# 9_Airframe-Wireless_-_Kopie.net
KiCad netlist of a schematic drawn in Altium Designer
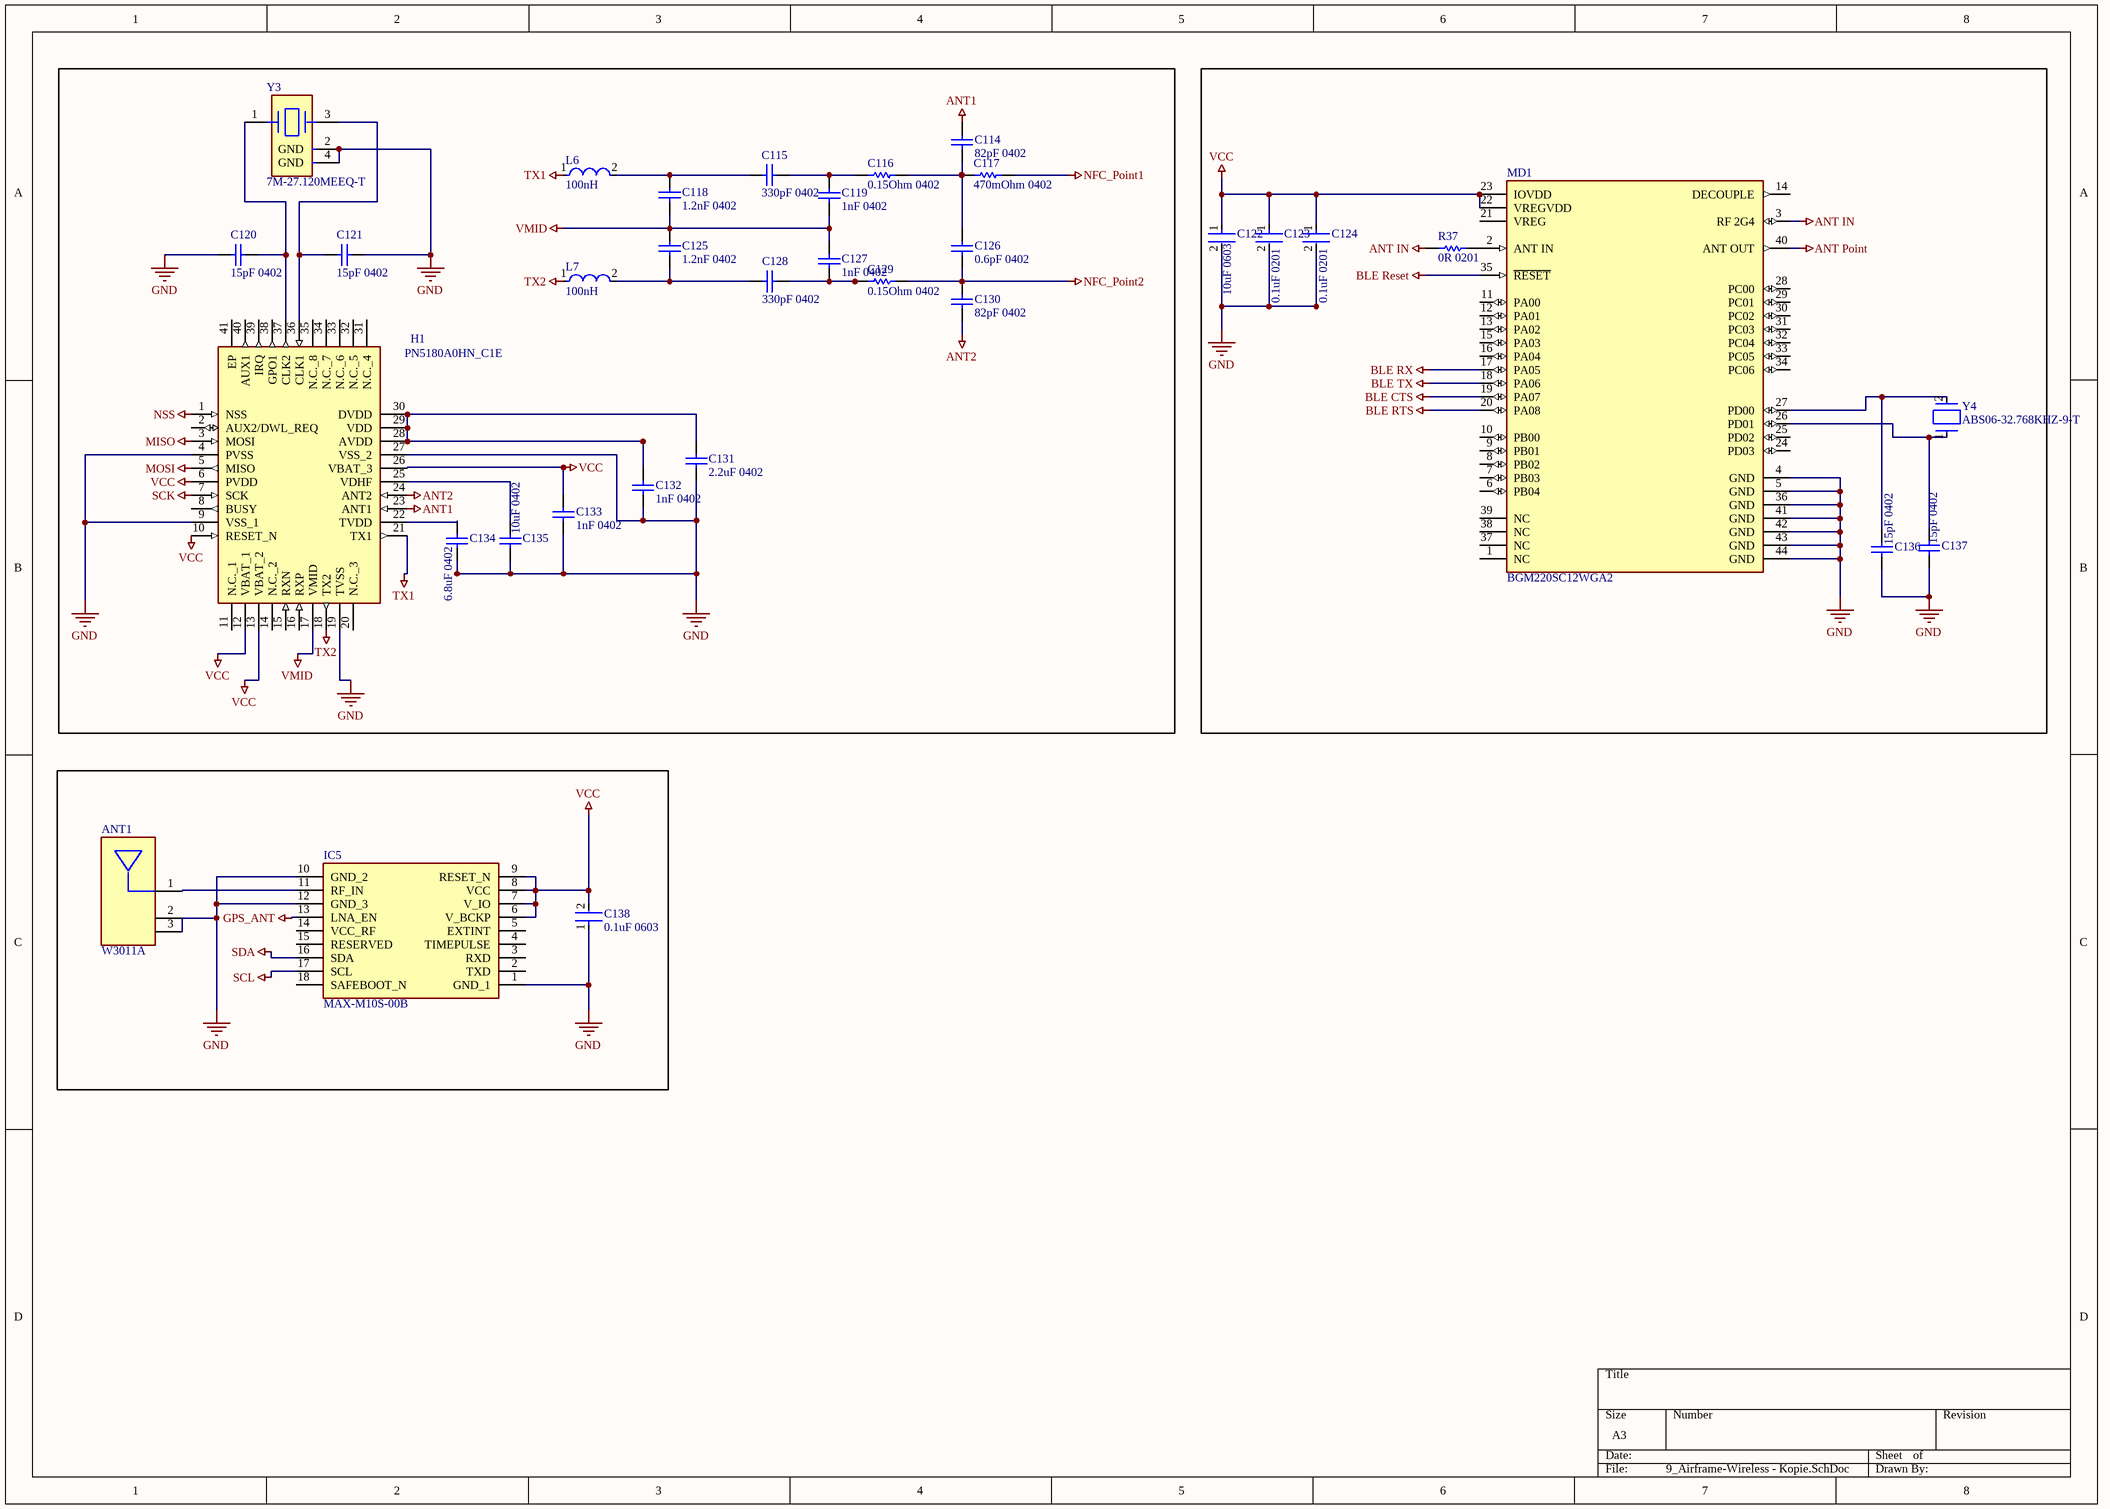
[diagram p0: 9_Airframe-Wireless - Kopie.SchDoc]

(export (version "E")
  (design (tool "Eeschema 10.0.6"))
  (components
    (comp (ref "ANT1")
      (value "W3011A")
      (footprint "FP-W3011A-MFG")
      (description "RF ANT 1.575GHZ CHIP SOLDER SMD")
      (fields
        (field (name "OCTOPART") "https://octopart.com/w3011a-pulse-10684180")
        (field (name "MANUFACTURER") "PulseLarsen Antennas")
      )
      (libsource (lib "Altium Content Vault") (part "6d32a7a60510b62759eb526d3a7a656"))
    )
    (comp (ref "C114")
      (value "82pF 0402")
      (footprint "CAPC1005X55X25ML5T10")
      (description "Chip Capacitor, 1 nF, +/- 10%, 50 V, -55 to 125 degC, 0402 (1005 Metric), RoHS, Tape and Reel")
      (fields (field (name "TOLERANCE") "10%"))
      (libsource (lib "Altium Content Vault") (part "CAP-NP-2"))
    )
    (comp (ref "C115")
      (value "330pF 0402")
      (footprint "CAPC1005X55X25ML5T10")
      (description "Chip Capacitor, 1 nF, +/- 10%, 50 V, -55 to 125 degC, 0402 (1005 Metric), RoHS, Tape and Reel")
      (fields (field (name "TOLERANCE") "10%"))
      (libsource (lib "Altium Content Vault") (part "CAP-NP-2"))
    )
    (comp (ref "C116")
      (value "0.15Ohm 0402")
      (footprint "RESC1608X55X25ML10T15")
      (description "Chip Resistor, 0 Ohm, +/- 5%, 0.1 W, -55 to 155 degC, 0603 (1608 Metric), RoHS, Tape and Reel")
      (fields (field (name "TOLERANCE") "5%") (field (name "MANUFACTURER") "Yageo"))
      (libsource (lib "Altium Content Vault") (part "RES-2"))
    )
    (comp (ref "C117")
      (value "470mOhm 0402")
      (footprint "RESC1608X55X25ML10T15")
      (description "Chip Resistor, 0 Ohm, +/- 5%, 0.1 W, -55 to 155 degC, 0603 (1608 Metric), RoHS, Tape and Reel")
      (fields (field (name "TOLERANCE") "5%") (field (name "MANUFACTURER") "Yageo"))
      (libsource (lib "Altium Content Vault") (part "RES-2"))
    )
    (comp (ref "C118")
      (value "1.2nF 0402")
      (footprint "CAPC1005X55X25ML5T10")
      (description "Chip Capacitor, 1 nF, +/- 10%, 50 V, -55 to 125 degC, 0402 (1005 Metric), RoHS, Tape and Reel")
      (fields (field (name "TOLERANCE") "10%"))
      (libsource (lib "Altium Content Vault") (part "CAP-NP-2"))
    )
    (comp (ref "C119")
      (value "1nF 0402")
      (footprint "CAPC1005X55X25ML5T10")
      (description "Chip Capacitor, 1 nF, +/- 10%, 50 V, -55 to 125 degC, 0402 (1005 Metric), RoHS, Tape and Reel")
      (fields (field (name "TOLERANCE") "10%"))
      (libsource (lib "Altium Content Vault") (part "CAP-NP-2"))
    )
    (comp (ref "C120")
      (value "15pF 0402")
      (footprint "CAPC1005X55X25ML5T10")
      (description "Chip Capacitor, 1 nF, +/- 10%, 50 V, -55 to 125 degC, 0402 (1005 Metric), RoHS, Tape and Reel")
      (fields (field (name "TOLERANCE") "10%"))
      (libsource (lib "Altium Content Vault") (part "CAP-NP-2"))
    )
    (comp (ref "C121")
      (value "15pF 0402")
      (footprint "CAPC1005X55X25ML5T10")
      (description "Chip Capacitor, 1 nF, +/- 10%, 50 V, -55 to 125 degC, 0402 (1005 Metric), RoHS, Tape and Reel")
      (fields (field (name "TOLERANCE") "10%"))
      (libsource (lib "Altium Content Vault") (part "CAP-NP-2"))
    )
    (comp (ref "C122")
      (value "10uF 0603")
      (footprint "FP-GRM188-0_2-IPC_C")
      (description "Chip Multilayer Ceramic Capacitors for General Purpose, 0603, 22uF, X5R, 15%, 20%, 10V")
      (fields (field (name "TOLERANCE") "20%"))
      (libsource (lib "Altium Content Vault") (part "11868f565c42a9108669ba33697ecf6"))
    )
    (comp (ref "C123")
      (value "0.1uF 0201")
      (footprint "FP-C0603-030-0_03-IPC_C")
      (description "Multilayer Ceramic Capacitors 220nF ±10% 6.3V X6S SMD 0201")
      (fields (field (name "TOLERANCE") "10%"))
      (libsource (lib "Altium Content Vault") (part "02cd4be3c70576c341d710602a673aa"))
    )
    (comp (ref "C124")
      (value "0.1uF 0201")
      (footprint "FP-C0603-030-0_03-IPC_C")
      (description "Multilayer Ceramic Capacitors 220nF ±10% 6.3V X6S SMD 0201")
      (fields (field (name "TOLERANCE") "10%"))
      (libsource (lib "Altium Content Vault") (part "02cd4be3c70576c341d710602a673aa"))
    )
    (comp (ref "C125")
      (value "1.2nF 0402")
      (footprint "CAPC1005X55X25ML5T10")
      (description "Chip Capacitor, 1 nF, +/- 10%, 50 V, -55 to 125 degC, 0402 (1005 Metric), RoHS, Tape and Reel")
      (fields (field (name "TOLERANCE") "10%"))
      (libsource (lib "Altium Content Vault") (part "CAP-NP-2"))
    )
    (comp (ref "C126")
      (value "0.6pF 0402")
      (footprint "CAPC1005X55X25ML5T10")
      (description "Chip Capacitor, 1 nF, +/- 10%, 50 V, -55 to 125 degC, 0402 (1005 Metric), RoHS, Tape and Reel")
      (fields (field (name "TOLERANCE") "10%"))
      (libsource (lib "Altium Content Vault") (part "CAP-NP-2"))
    )
    (comp (ref "C127")
      (value "1nF 0402")
      (footprint "CAPC1005X55X25ML5T10")
      (description "Chip Capacitor, 1 nF, +/- 10%, 50 V, -55 to 125 degC, 0402 (1005 Metric), RoHS, Tape and Reel")
      (fields (field (name "TOLERANCE") "10%"))
      (libsource (lib "Altium Content Vault") (part "CAP-NP-2"))
    )
    (comp (ref "C128")
      (value "330pF 0402")
      (footprint "CAPC1005X55X25ML5T10")
      (description "Chip Capacitor, 1 nF, +/- 10%, 50 V, -55 to 125 degC, 0402 (1005 Metric), RoHS, Tape and Reel")
      (fields (field (name "TOLERANCE") "10%"))
      (libsource (lib "Altium Content Vault") (part "CAP-NP-2"))
    )
    (comp (ref "C129")
      (value "0.15Ohm 0402")
      (footprint "RESC1608X55X25ML10T15")
      (description "Chip Resistor, 0 Ohm, +/- 5%, 0.1 W, -55 to 155 degC, 0603 (1608 Metric), RoHS, Tape and Reel")
      (fields (field (name "TOLERANCE") "5%") (field (name "MANUFACTURER") "Yageo"))
      (libsource (lib "Altium Content Vault") (part "RES-2"))
    )
    (comp (ref "C130")
      (value "82pF 0402")
      (footprint "CAPC1005X55X25ML5T10")
      (description "Chip Capacitor, 1 nF, +/- 10%, 50 V, -55 to 125 degC, 0402 (1005 Metric), RoHS, Tape and Reel")
      (fields (field (name "TOLERANCE") "10%"))
      (libsource (lib "Altium Content Vault") (part "CAP-NP-2"))
    )
    (comp (ref "C131")
      (value "2.2uF 0402")
      (footprint "CAPC1005X55X25ML5T10")
      (description "Chip Capacitor, 1 nF, +/- 10%, 50 V, -55 to 125 degC, 0402 (1005 Metric), RoHS, Tape and Reel")
      (fields (field (name "TOLERANCE") "10%"))
      (libsource (lib "Altium Content Vault") (part "CAP-NP-2"))
    )
    (comp (ref "C132")
      (value "1nF 0402")
      (footprint "CAPC1005X55X25ML5T10")
      (description "Chip Capacitor, 1 nF, +/- 10%, 50 V, -55 to 125 degC, 0402 (1005 Metric), RoHS, Tape and Reel")
      (fields (field (name "TOLERANCE") "10%"))
      (libsource (lib "Altium Content Vault") (part "CAP-NP-2"))
    )
    (comp (ref "C133")
      (value "1nF 0402")
      (footprint "CAPC1005X55X25ML5T10")
      (description "Chip Capacitor, 1 nF, +/- 10%, 50 V, -55 to 125 degC, 0402 (1005 Metric), RoHS, Tape and Reel")
      (fields (field (name "TOLERANCE") "10%"))
      (libsource (lib "Altium Content Vault") (part "CAP-NP-2"))
    )
    (comp (ref "C134")
      (value "6.8uF 0402")
      (footprint "CAPC1005X55X25ML5T10")
      (description "Chip Capacitor, 1 nF, +/- 10%, 50 V, -55 to 125 degC, 0402 (1005 Metric), RoHS, Tape and Reel")
      (fields (field (name "TOLERANCE") "10%"))
      (libsource (lib "Altium Content Vault") (part "CAP-NP-2"))
    )
    (comp (ref "C135")
      (value "10uF 0402")
      (footprint "CAPC1005X55X25ML5T10")
      (description "Chip Capacitor, 1 nF, +/- 10%, 50 V, -55 to 125 degC, 0402 (1005 Metric), RoHS, Tape and Reel")
      (fields (field (name "TOLERANCE") "10%"))
      (libsource (lib "Altium Content Vault") (part "CAP-NP-2"))
    )
    (comp (ref "C136")
      (value "15pF 0402")
      (footprint "CAPC1005X55X25ML5T10")
      (description "Chip Capacitor, 1 nF, +/- 10%, 50 V, -55 to 125 degC, 0402 (1005 Metric), RoHS, Tape and Reel")
      (fields (field (name "TOLERANCE") "10%"))
      (libsource (lib "Altium Content Vault") (part "CAP-NP-2"))
    )
    (comp (ref "C137")
      (value "15pF 0402")
      (footprint "CAPC1005X55X25ML5T10")
      (description "Chip Capacitor, 1 nF, +/- 10%, 50 V, -55 to 125 degC, 0402 (1005 Metric), RoHS, Tape and Reel")
      (fields (field (name "TOLERANCE") "10%"))
      (libsource (lib "Altium Content Vault") (part "CAP-NP-2"))
    )
    (comp (ref "C138")
      (value "0.1uF 0603")
      (footprint "FP-C0603C-CF-MFG")
      (description "CAP CER 0.1UF 50V X7R 0603")
      (fields (field (name "TOLERANCE") "0.1") (field (name "MANUFACTURER") "KEMET"))
      (libsource (lib "Altium Content Vault") (part "b4654b650e69147ec39a6b967a45e02"))
    )
    (comp (ref "H1")
      (value "PN5180A0HN_C1E")
      (footprint "SamacSys:QFN50P600X600X100-41N-D")
      (description "Hardware")
      (fields
        (field (name "MANUFACTURER_PART_NUMBER") "PN5180A0HN/C1E")
        (field (name "MOUSER PART NUMBER") "771-PN5180A0HN/C1E")
      )
      (libsource (lib "*") (part "PN5180A0HN_C1E"))
    )
    (comp (ref "IC5")
      (value "MAX-M10S-00B")
      (footprint "SamacSys:MAXM10S00B")
      (description "Integrated Circuit")
      (fields (field (name "MOUSER PART NUMBER") "377-MAX-M10S-00B"))
      (libsource (lib "*") (part "MAX-M10S-00B"))
    )
    (comp (ref "L6")
      (value "100nH")
      (footprint "FP-LQM18NN_00-IPC_C")
      (description "Multilayer Type Inductor for General Circuits, 0603 (1608), 100nH, 10%, 0.5Ω, 50mA")
      (fields (field (name "TOLERANCE") "10%"))
      (libsource (lib "Altium Content Vault") (part "725321dda6339637d4d059423bc1c3c"))
    )
    (comp (ref "L7")
      (value "100nH")
      (footprint "FP-LQM18NN_00-IPC_C")
      (description "Multilayer Type Inductor for General Circuits, 0603 (1608), 100nH, 10%, 0.5Ω, 50mA")
      (fields (field (name "TOLERANCE") "10%"))
      (libsource (lib "Altium Content Vault") (part "725321dda6339637d4d059423bc1c3c"))
    )
    (comp (ref "MD1")
      (value "BGM220SC12WGA2")
      (footprint "FP-BGM220SC12WGA2-MFG")
      (description "WIRELESS GECKO, BLUETOOTH SIP MO")
      (libsource (lib "Altium Content Vault") (part "a291eb52f76d4e7f0fdfcca3ce5d403"))
    )
    (comp (ref "R37")
      (value "0R 0201")
      (footprint "RESC0603X28X15NL05T05")
      (fields (field (name "MANUFACTURER") "Vishay") (field (name "PART NUMBER") "CRCW0201100RFNED"))
      (libsource (lib "Altium Content Vault") (part "RES"))
    )
    (comp (ref "Y3")
      (value "7M-27.120MEEQ-T")
      (footprint "FP-7M-MFG")
      (description "Crystal 27.12MHz, 10ppm, 10pF, 50Ω")
      (fields (field (name "TOLERANCE") "10ppm"))
      (libsource (lib "Altium Content Vault") (part "41079aabb0e87794b56622915be14ed"))
    )
    (comp (ref "Y4")
      (value "ABS06-32.768KHZ-9-T")
      (footprint "FP-ABS06-MFG")
      (description "Crystal 32.768kHz ±20ppm (Tol) 9pF FUND 90kΩ 2-Pin Mini-CSMD T/R")
      (fields (field (name "TOLERANCE") "20ppm"))
      (libsource (lib "Altium Content Vault") (part "c23a69dc6c9e2f18f2079038eb95dd1"))
    )
  )
  (nets
    (net (code "1") (name "ANT IN") (class "Default")
      (node (ref "MD1") (pin "3") (pinfunction "RF_2G4_3") (pintype "bidirectional"))
      (node (ref "R37") (pin "2") (pinfunction "2_2") (pintype "passive"))
    )
    (net (code "2") (name "ANT Point") (class "Default")
      (node (ref "MD1") (pin "40") (pinfunction "ANT_OUT_40") (pintype "output"))
    )
    (net (code "3") (name "ANT1") (class "Default")
      (node (ref "C114") (pin "1") (pinfunction "1_1") (pintype "passive"))
      (node (ref "H1") (pin "23") (pinfunction "ANT1_23") (pintype "input"))
    )
    (net (code "4") (name "ANT2") (class "Default")
      (node (ref "C130") (pin "2") (pinfunction "2_2") (pintype "passive"))
      (node (ref "H1") (pin "24") (pinfunction "ANT2_24") (pintype "input"))
    )
    (net (code "5") (name "BLE CTS") (class "Default")
      (node (ref "MD1") (pin "19") (pinfunction "PA07_19") (pintype "bidirectional"))
    )
    (net (code "6") (name "BLE RTS") (class "Default")
      (node (ref "MD1") (pin "20") (pinfunction "PA08_20") (pintype "bidirectional"))
    )
    (net (code "7") (name "BLE RX") (class "Default")
      (node (ref "MD1") (pin "17") (pinfunction "PA05_17") (pintype "bidirectional"))
    )
    (net (code "8") (name "BLE Reset") (class "Default")
      (node (ref "MD1") (pin "35") (pinfunction "~{RESET}_35") (pintype "input"))
    )
    (net (code "9") (name "BLE TX") (class "Default")
      (node (ref "MD1") (pin "18") (pinfunction "PA06_18") (pintype "bidirectional"))
    )
    (net (code "10") (name "GND") (class "Default")
      (node (ref "ANT1") (pin "2") (pinfunction "GND_2") (pintype "power_in"))
      (node (ref "ANT1") (pin "3") (pinfunction "GND_3") (pintype "power_in"))
      (node (ref "C120") (pin "1") (pinfunction "1_1") (pintype "passive"))
      (node (ref "C121") (pin "2") (pinfunction "2_2") (pintype "passive"))
      (node (ref "C122") (pin "2") (pinfunction "2_2") (pintype "passive"))
      (node (ref "C123") (pin "2") (pinfunction "2_2") (pintype "passive"))
      (node (ref "C124") (pin "2") (pinfunction "2_2") (pintype "passive"))
      (node (ref "C131") (pin "2") (pinfunction "2_2") (pintype "passive"))
      (node (ref "C132") (pin "2") (pinfunction "2_2") (pintype "passive"))
      (node (ref "C133") (pin "2") (pinfunction "2_2") (pintype "passive"))
      (node (ref "C134") (pin "2") (pinfunction "2_2") (pintype "passive"))
      (node (ref "C135") (pin "2") (pinfunction "2_2") (pintype "passive"))
      (node (ref "C136") (pin "1") (pinfunction "1_1") (pintype "passive"))
      (node (ref "C137") (pin "1") (pinfunction "1_1") (pintype "passive"))
      (node (ref "C138") (pin "1") (pinfunction "1_1") (pintype "passive"))
      (node (ref "H1") (pin "19") (pinfunction "TVSS_19") (pintype "power_in"))
      (node (ref "H1") (pin "27") (pinfunction "VSS_2_27") (pintype "power_in"))
      (node (ref "H1") (pin "4") (pinfunction "PVSS_4") (pintype "power_in"))
      (node (ref "H1") (pin "9") (pinfunction "VSS_1_9") (pintype "power_in"))
      (node (ref "IC5") (pin "1") (pinfunction "GND_1_1") (pintype "passive"))
      (node (ref "IC5") (pin "10") (pinfunction "GND_2_10") (pintype "passive"))
      (node (ref "IC5") (pin "12") (pinfunction "GND_3_12") (pintype "passive"))
      (node (ref "MD1") (pin "36") (pinfunction "GND_36") (pintype "power_in"))
      (node (ref "MD1") (pin "4") (pinfunction "GND_4") (pintype "power_in"))
      (node (ref "MD1") (pin "41") (pinfunction "GND_41") (pintype "power_in"))
      (node (ref "MD1") (pin "42") (pinfunction "GND_42") (pintype "power_in"))
      (node (ref "MD1") (pin "43") (pinfunction "GND_43") (pintype "power_in"))
      (node (ref "MD1") (pin "44") (pinfunction "GND_44") (pintype "power_in"))
      (node (ref "MD1") (pin "5") (pinfunction "GND_5") (pintype "power_in"))
      (node (ref "Y3") (pin "2") (pinfunction "GND_2") (pintype "power_in"))
      (node (ref "Y3") (pin "4") (pinfunction "GND_4") (pintype "power_in"))
    )
    (net (code "11") (name "GPS_ANT") (class "Default")
      (node (ref "IC5") (pin "13") (pinfunction "LNA_EN_13") (pintype "passive"))
    )
    (net (code "12") (name "MISO") (class "Default")
      (node (ref "H1") (pin "3") (pinfunction "MOSI_3") (pintype "input"))
    )
    (net (code "13") (name "MOSI") (class "Default")
      (node (ref "H1") (pin "5") (pinfunction "MISO_5") (pintype "output"))
    )
    (net (code "14") (name "NFC_Point1") (class "Default")
      (node (ref "C117") (pin "1") (pinfunction "1_1") (pintype "passive"))
    )
    (net (code "15") (name "NFC_Point2") (class "Default")
      (node (ref "C126") (pin "2") (pinfunction "2_2") (pintype "passive"))
      (node (ref "C129") (pin "1") (pinfunction "1_1") (pintype "passive"))
      (node (ref "C130") (pin "1") (pinfunction "1_1") (pintype "passive"))
    )
    (net (code "16") (name "NSS") (class "Default")
      (node (ref "H1") (pin "1") (pinfunction "NSS_1") (pintype "input"))
    )
    (net (code "17") (name "Net-(ANT1-Feed)") (class "Default")
      (node (ref "ANT1") (pin "1") (pinfunction "Feed_1") (pintype "power_in"))
      (node (ref "IC5") (pin "11") (pinfunction "RF_IN_11") (pintype "passive"))
    )
    (net (code "18") (name "Net-(C114-Pad2)") (class "Default")
      (node (ref "C114") (pin "2") (pinfunction "2_2") (pintype "passive"))
      (node (ref "C116") (pin "1") (pinfunction "1_1") (pintype "passive"))
      (node (ref "C117") (pin "2") (pinfunction "2_2") (pintype "passive"))
      (node (ref "C126") (pin "1") (pinfunction "1_1") (pintype "passive"))
    )
    (net (code "19") (name "Net-(C115-Pad1)") (class "Default")
      (node (ref "C115") (pin "1") (pinfunction "1_1") (pintype "passive"))
      (node (ref "C118") (pin "1") (pinfunction "1_1") (pintype "passive"))
      (node (ref "L6") (pin "2") (pinfunction "2_2") (pintype "passive"))
    )
    (net (code "20") (name "Net-(C115-Pad2)") (class "Default")
      (node (ref "C115") (pin "2") (pinfunction "2_2") (pintype "passive"))
      (node (ref "C116") (pin "2") (pinfunction "2_2") (pintype "passive"))
      (node (ref "C119") (pin "2") (pinfunction "2_2") (pintype "passive"))
    )
    (net (code "21") (name "Net-(C125-Pad2)") (class "Default")
      (node (ref "C125") (pin "2") (pinfunction "2_2") (pintype "passive"))
      (node (ref "C128") (pin "1") (pinfunction "1_1") (pintype "passive"))
      (node (ref "L7") (pin "2") (pinfunction "2_2") (pintype "passive"))
    )
    (net (code "22") (name "Net-(C127-Pad1)") (class "Default")
      (node (ref "C127") (pin "1") (pinfunction "1_1") (pintype "passive"))
      (node (ref "C128") (pin "2") (pinfunction "2_2") (pintype "passive"))
      (node (ref "C129") (pin "2") (pinfunction "2_2") (pintype "passive"))
    )
    (net (code "23") (name "Net-(H1-AVDD)") (class "Default")
      (node (ref "C131") (pin "1") (pinfunction "1_1") (pintype "passive"))
      (node (ref "C132") (pin "1") (pinfunction "1_1") (pintype "passive"))
      (node (ref "H1") (pin "28") (pinfunction "AVDD_28") (pintype "power_in"))
      (node (ref "H1") (pin "29") (pinfunction "VDD_29") (pintype "power_in"))
      (node (ref "H1") (pin "30") (pinfunction "DVDD_30") (pintype "power_in"))
    )
    (net (code "24") (name "Net-(H1-CLK1)") (class "Default")
      (node (ref "C121") (pin "1") (pinfunction "1_1") (pintype "passive"))
      (node (ref "H1") (pin "36") (pinfunction "CLK1_36") (pintype "input"))
      (node (ref "Y3") (pin "3") (pinfunction "3_3") (pintype "passive"))
    )
    (net (code "25") (name "Net-(H1-CLK2)") (class "Default")
      (node (ref "C120") (pin "2") (pinfunction "2_2") (pintype "passive"))
      (node (ref "H1") (pin "37") (pinfunction "CLK2_37") (pintype "output"))
      (node (ref "Y3") (pin "1") (pinfunction "1_1") (pintype "passive"))
    )
    (net (code "26") (name "Net-(H1-TVDD)") (class "Default")
      (node (ref "C134") (pin "1") (pinfunction "1_1") (pintype "passive"))
      (node (ref "H1") (pin "22") (pinfunction "TVDD_22") (pintype "power_in"))
    )
    (net (code "27") (name "Net-(H1-VDHF)") (class "Default")
      (node (ref "C135") (pin "1") (pinfunction "1_1") (pintype "passive"))
      (node (ref "H1") (pin "25") (pinfunction "VDHF_25") (pintype "power_in"))
    )
    (net (code "28") (name "Net-(MD1-ANT_IN)") (class "Default")
      (node (ref "MD1") (pin "2") (pinfunction "ANT_IN_2") (pintype "input"))
      (node (ref "R37") (pin "1") (pinfunction "1_1") (pintype "passive"))
    )
    (net (code "29") (name "Net-(MD1-PD00)") (class "Default")
      (node (ref "C136") (pin "2") (pinfunction "2_2") (pintype "passive"))
      (node (ref "MD1") (pin "27") (pinfunction "PD00_27") (pintype "bidirectional"))
      (node (ref "Y4") (pin "2") (pinfunction "2_2") (pintype "passive"))
    )
    (net (code "30") (name "Net-(MD1-PD01)") (class "Default")
      (node (ref "C137") (pin "2") (pinfunction "2_2") (pintype "passive"))
      (node (ref "MD1") (pin "26") (pinfunction "PD01_26") (pintype "bidirectional"))
      (node (ref "Y4") (pin "1") (pinfunction "1_1") (pintype "passive"))
    )
    (net (code "31") (name "SCK") (class "Default")
      (node (ref "H1") (pin "7") (pinfunction "SCK_7") (pintype "input"))
    )
    (net (code "32") (name "SCL") (class "Default")
      (node (ref "IC5") (pin "17") (pinfunction "SCL_17") (pintype "passive"))
    )
    (net (code "33") (name "SDA") (class "Default")
      (node (ref "IC5") (pin "16") (pinfunction "SDA_16") (pintype "passive"))
    )
    (net (code "34") (name "TX1") (class "Default")
      (node (ref "H1") (pin "21") (pinfunction "TX1_21") (pintype "output"))
      (node (ref "L6") (pin "1") (pinfunction "1_1") (pintype "passive"))
    )
    (net (code "35") (name "TX2") (class "Default")
      (node (ref "H1") (pin "18") (pinfunction "TX2_18") (pintype "output"))
      (node (ref "L7") (pin "1") (pinfunction "1_1") (pintype "passive"))
    )
    (net (code "36") (name "VCC") (class "Default")
      (node (ref "C122") (pin "1") (pinfunction "1_1") (pintype "passive"))
      (node (ref "C123") (pin "1") (pinfunction "1_1") (pintype "passive"))
      (node (ref "C124") (pin "1") (pinfunction "1_1") (pintype "passive"))
      (node (ref "C133") (pin "1") (pinfunction "1_1") (pintype "passive"))
      (node (ref "C138") (pin "2") (pinfunction "2_2") (pintype "passive"))
      (node (ref "H1") (pin "10") (pinfunction "RESET_N_10") (pintype "input"))
      (node (ref "H1") (pin "12") (pinfunction "VBAT_1_12") (pintype "power_in"))
      (node (ref "H1") (pin "13") (pinfunction "VBAT_2_13") (pintype "power_in"))
      (node (ref "H1") (pin "26") (pinfunction "VBAT_3_26") (pintype "power_in"))
      (node (ref "H1") (pin "6") (pinfunction "PVDD_6") (pintype "power_in"))
      (node (ref "IC5") (pin "6") (pinfunction "V_BCKP_6") (pintype "passive"))
      (node (ref "IC5") (pin "7") (pinfunction "V_IO_7") (pintype "passive"))
      (node (ref "IC5") (pin "8") (pinfunction "VCC_8") (pintype "passive"))
      (node (ref "IC5") (pin "9") (pinfunction "RESET_N_9") (pintype "passive"))
      (node (ref "MD1") (pin "22") (pinfunction "VREGVDD_22") (pintype "power_in"))
      (node (ref "MD1") (pin "23") (pinfunction "IOVDD_23") (pintype "power_in"))
    )
    (net (code "37") (name "VMID") (class "Default")
      (node (ref "C118") (pin "2") (pinfunction "2_2") (pintype "passive"))
      (node (ref "C119") (pin "1") (pinfunction "1_1") (pintype "passive"))
      (node (ref "C125") (pin "1") (pinfunction "1_1") (pintype "passive"))
      (node (ref "C127") (pin "2") (pinfunction "2_2") (pintype "passive"))
      (node (ref "H1") (pin "17") (pinfunction "VMID_17") (pintype "power_in"))
    )
    (net (code "38") (name "unconnected-(H1-AUX1-Pad40)") (class "Default")
      (node (ref "H1") (pin "40") (pinfunction "AUX1_40") (pintype "output"))
    )
    (net (code "39") (name "unconnected-(H1-AUX2{slash}DWL_REQ-Pad2)") (class "Default")
      (node (ref "H1") (pin "2") (pinfunction "AUX2/DWL_REQ_2") (pintype "bidirectional"))
    )
    (net (code "40") (name "unconnected-(H1-BUSY-Pad8)") (class "Default")
      (node (ref "H1") (pin "8") (pinfunction "BUSY_8") (pintype "output"))
    )
    (net (code "41") (name "unconnected-(H1-EP-Pad41)") (class "Default")
      (node (ref "H1") (pin "41") (pinfunction "EP_41") (pintype "passive"))
    )
    (net (code "42") (name "unconnected-(H1-GPO1-Pad38)") (class "Default")
      (node (ref "H1") (pin "38") (pinfunction "GPO1_38") (pintype "output"))
    )
    (net (code "43") (name "unconnected-(H1-IRQ-Pad39)") (class "Default")
      (node (ref "H1") (pin "39") (pinfunction "IRQ_39") (pintype "output"))
    )
    (net (code "44") (name "unconnected-(H1-N.C._1-Pad11)") (class "Default")
      (node (ref "H1") (pin "11") (pinfunction "N.C._1_11") (pintype "passive"))
    )
    (net (code "45") (name "unconnected-(H1-N.C._2-Pad14)") (class "Default")
      (node (ref "H1") (pin "14") (pinfunction "N.C._2_14") (pintype "passive"))
    )
    (net (code "46") (name "unconnected-(H1-N.C._3-Pad20)") (class "Default")
      (node (ref "H1") (pin "20") (pinfunction "N.C._3_20") (pintype "passive"))
    )
    (net (code "47") (name "unconnected-(H1-N.C._4-Pad31)") (class "Default")
      (node (ref "H1") (pin "31") (pinfunction "N.C._4_31") (pintype "passive"))
    )
    (net (code "48") (name "unconnected-(H1-N.C._5-Pad32)") (class "Default")
      (node (ref "H1") (pin "32") (pinfunction "N.C._5_32") (pintype "passive"))
    )
    (net (code "49") (name "unconnected-(H1-N.C._6-Pad33)") (class "Default")
      (node (ref "H1") (pin "33") (pinfunction "N.C._6_33") (pintype "passive"))
    )
    (net (code "50") (name "unconnected-(H1-N.C._7-Pad34)") (class "Default")
      (node (ref "H1") (pin "34") (pinfunction "N.C._7_34") (pintype "passive"))
    )
    (net (code "51") (name "unconnected-(H1-N.C._8-Pad35)") (class "Default")
      (node (ref "H1") (pin "35") (pinfunction "N.C._8_35") (pintype "passive"))
    )
    (net (code "52") (name "unconnected-(H1-RXN-Pad15)") (class "Default")
      (node (ref "H1") (pin "15") (pinfunction "RXN_15") (pintype "input"))
    )
    (net (code "53") (name "unconnected-(H1-RXP-Pad16)") (class "Default")
      (node (ref "H1") (pin "16") (pinfunction "RXP_16") (pintype "input"))
    )
    (net (code "54") (name "unconnected-(IC5-EXTINT-Pad5)") (class "Default")
      (node (ref "IC5") (pin "5") (pinfunction "EXTINT_5") (pintype "passive"))
    )
    (net (code "55") (name "unconnected-(IC5-RESERVED-Pad15)") (class "Default")
      (node (ref "IC5") (pin "15") (pinfunction "RESERVED_15") (pintype "passive"))
    )
    (net (code "56") (name "unconnected-(IC5-RXD-Pad3)") (class "Default")
      (node (ref "IC5") (pin "3") (pinfunction "RXD_3") (pintype "passive"))
    )
    (net (code "57") (name "unconnected-(IC5-SAFEBOOT_N-Pad18)") (class "Default")
      (node (ref "IC5") (pin "18") (pinfunction "SAFEBOOT_N_18") (pintype "passive"))
    )
    (net (code "58") (name "unconnected-(IC5-TIMEPULSE-Pad4)") (class "Default")
      (node (ref "IC5") (pin "4") (pinfunction "TIMEPULSE_4") (pintype "passive"))
    )
    (net (code "59") (name "unconnected-(IC5-TXD-Pad2)") (class "Default")
      (node (ref "IC5") (pin "2") (pinfunction "TXD_2") (pintype "passive"))
    )
    (net (code "60") (name "unconnected-(IC5-VCC_RF-Pad14)") (class "Default")
      (node (ref "IC5") (pin "14") (pinfunction "VCC_RF_14") (pintype "passive"))
    )
    (net (code "61") (name "unconnected-(MD1-DECOUPLE-Pad14)") (class "Default")
      (node (ref "MD1") (pin "14") (pinfunction "DECOUPLE_14") (pintype "output"))
    )
    (net (code "62") (name "unconnected-(MD1-NC-Pad1)") (class "Default")
      (node (ref "MD1") (pin "1") (pinfunction "NC_1") (pintype "passive"))
    )
    (net (code "63") (name "unconnected-(MD1-NC-Pad37)") (class "Default")
      (node (ref "MD1") (pin "37") (pinfunction "NC_37") (pintype "passive"))
    )
    (net (code "64") (name "unconnected-(MD1-NC-Pad38)") (class "Default")
      (node (ref "MD1") (pin "38") (pinfunction "NC_38") (pintype "passive"))
    )
    (net (code "65") (name "unconnected-(MD1-NC-Pad39)") (class "Default")
      (node (ref "MD1") (pin "39") (pinfunction "NC_39") (pintype "passive"))
    )
    (net (code "66") (name "unconnected-(MD1-PA00-Pad11)") (class "Default")
      (node (ref "MD1") (pin "11") (pinfunction "PA00_11") (pintype "bidirectional"))
    )
    (net (code "67") (name "unconnected-(MD1-PA01-Pad12)") (class "Default")
      (node (ref "MD1") (pin "12") (pinfunction "PA01_12") (pintype "bidirectional"))
    )
    (net (code "68") (name "unconnected-(MD1-PA02-Pad13)") (class "Default")
      (node (ref "MD1") (pin "13") (pinfunction "PA02_13") (pintype "bidirectional"))
    )
    (net (code "69") (name "unconnected-(MD1-PA03-Pad15)") (class "Default")
      (node (ref "MD1") (pin "15") (pinfunction "PA03_15") (pintype "bidirectional"))
    )
    (net (code "70") (name "unconnected-(MD1-PA04-Pad16)") (class "Default")
      (node (ref "MD1") (pin "16") (pinfunction "PA04_16") (pintype "bidirectional"))
    )
    (net (code "71") (name "unconnected-(MD1-PB00-Pad10)") (class "Default")
      (node (ref "MD1") (pin "10") (pinfunction "PB00_10") (pintype "bidirectional"))
    )
    (net (code "72") (name "unconnected-(MD1-PB01-Pad9)") (class "Default")
      (node (ref "MD1") (pin "9") (pinfunction "PB01_9") (pintype "bidirectional"))
    )
    (net (code "73") (name "unconnected-(MD1-PB02-Pad8)") (class "Default")
      (node (ref "MD1") (pin "8") (pinfunction "PB02_8") (pintype "bidirectional"))
    )
    (net (code "74") (name "unconnected-(MD1-PB03-Pad7)") (class "Default")
      (node (ref "MD1") (pin "7") (pinfunction "PB03_7") (pintype "bidirectional"))
    )
    (net (code "75") (name "unconnected-(MD1-PB04-Pad6)") (class "Default")
      (node (ref "MD1") (pin "6") (pinfunction "PB04_6") (pintype "bidirectional"))
    )
    (net (code "76") (name "unconnected-(MD1-PC00-Pad28)") (class "Default")
      (node (ref "MD1") (pin "28") (pinfunction "PC00_28") (pintype "bidirectional"))
    )
    (net (code "77") (name "unconnected-(MD1-PC01-Pad29)") (class "Default")
      (node (ref "MD1") (pin "29") (pinfunction "PC01_29") (pintype "bidirectional"))
    )
    (net (code "78") (name "unconnected-(MD1-PC02-Pad30)") (class "Default")
      (node (ref "MD1") (pin "30") (pinfunction "PC02_30") (pintype "bidirectional"))
    )
    (net (code "79") (name "unconnected-(MD1-PC03-Pad31)") (class "Default")
      (node (ref "MD1") (pin "31") (pinfunction "PC03_31") (pintype "bidirectional"))
    )
    (net (code "80") (name "unconnected-(MD1-PC04-Pad32)") (class "Default")
      (node (ref "MD1") (pin "32") (pinfunction "PC04_32") (pintype "bidirectional"))
    )
    (net (code "81") (name "unconnected-(MD1-PC05-Pad33)") (class "Default")
      (node (ref "MD1") (pin "33") (pinfunction "PC05_33") (pintype "bidirectional"))
    )
    (net (code "82") (name "unconnected-(MD1-PC06-Pad34)") (class "Default")
      (node (ref "MD1") (pin "34") (pinfunction "PC06_34") (pintype "bidirectional"))
    )
    (net (code "83") (name "unconnected-(MD1-PD02-Pad25)") (class "Default")
      (node (ref "MD1") (pin "25") (pinfunction "PD02_25") (pintype "bidirectional"))
    )
    (net (code "84") (name "unconnected-(MD1-PD03-Pad24)") (class "Default")
      (node (ref "MD1") (pin "24") (pinfunction "PD03_24") (pintype "bidirectional"))
    )
    (net (code "85") (name "unconnected-(MD1-VREG-Pad21)") (class "Default")
      (node (ref "MD1") (pin "21") (pinfunction "VREG_21") (pintype "power_in"))
    )
  )
)
